# Sheet1.net
KiCad netlist of a schematic drawn in Altium Designer
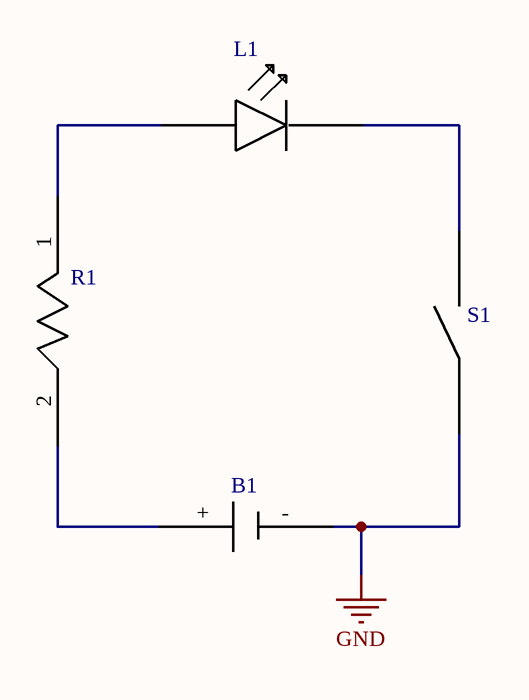
[diagram p0: Sheet1.SchDoc]

(export (version "E")
  (design (tool "Eeschema 10.0.6"))
  (components
    (comp (ref "B1") (value "~") (footprint "Battery") (libsource (lib "PCB2_session") (part "Battery")))
    (comp (ref "L1") (value "LED") (footprint "LED") (libsource (lib "PCB2_session") (part "LED")))
    (comp (ref "R1")
      (value "Through Hole Res 1K")
      (footprint "Through Hole Res 1K")
      (libsource (lib "PCB2_session") (part "Through Hole Res 1K"))
    )
    (comp (ref "S1")
      (value "~")
      (footprint "Switch")
      (fields (field (name "MANUFACTURER") "Texas Insrument"))
      (libsource (lib "PCB2_session") (part "Switch"))
    )
  )
  (nets
    (net (code "1") (name "GND") (class "Default")
      (node (ref "B1") (pin "-") (pintype "passive"))
      (node (ref "S1") (pin "2") (pintype "passive"))
    )
    (net (code "2") (name "Net-(B1-Pad+)") (class "Default")
      (node (ref "B1") (pin "+") (pintype "passive"))
      (node (ref "R1") (pin "2") (pinfunction "2_2") (pintype "passive"))
    )
    (net (code "3") (name "Net-(L1-Pad1)") (class "Default")
      (node (ref "L1") (pin "1") (pintype "passive"))
      (node (ref "S1") (pin "1") (pintype "passive"))
    )
    (net (code "4") (name "Net-(L1-Pad2)") (class "Default")
      (node (ref "L1") (pin "2") (pintype "passive"))
      (node (ref "R1") (pin "1") (pinfunction "1_1") (pintype "passive"))
    )
  )
)
